# arduinoRGBkaleidoscopeCkt2_v3.net
KiCad netlist of a schematic drawn in EAGLE
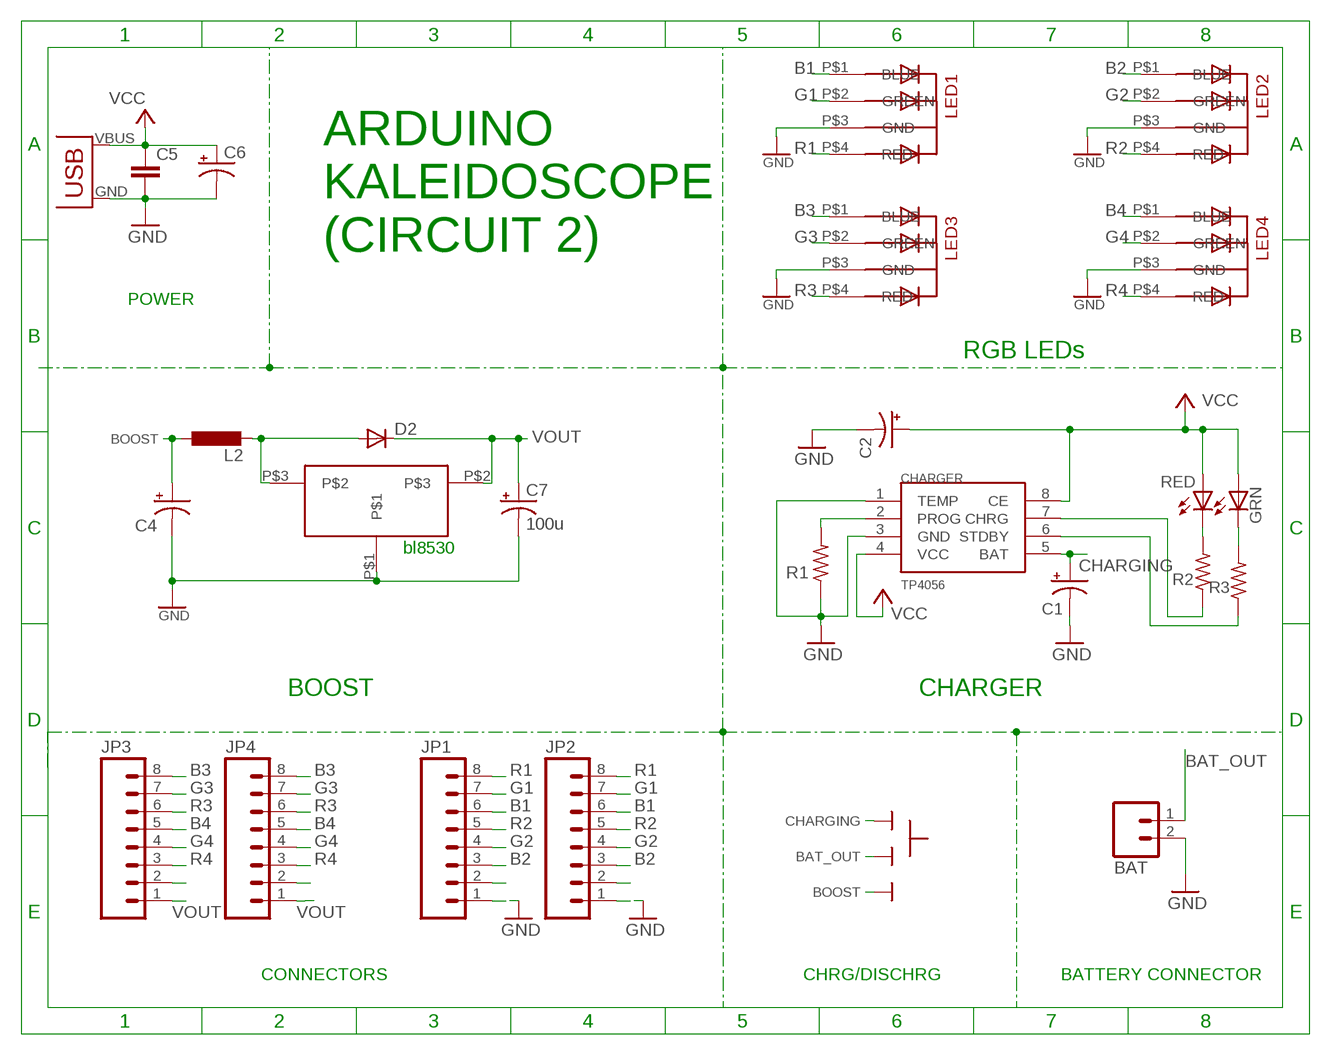
[diagram p0: schematic, sheet 1]

(export (version "E")
  (design (tool "Eeschema 10.0.6"))
  (components
    (comp (ref "BAT")
      (value "M02")
      (footprint "eagle-import:02P")
      (libsource (lib "eagle-import") (part "M02"))
    )
    (comp (ref "BOOST")
      (value "BL8530_5V")
      (footprint "eagle-import:BL8530_5V")
      (libsource (lib "eagle-import") (part "BL8530_5V"))
    )
    (comp (ref "C1")
      (value "10u")
      (footprint "eagle-import:C_6032-28R")
      (libsource (lib "eagle-import") (part "CAP_POL_10V"))
    )
    (comp (ref "C2")
      (value "10u")
      (footprint "eagle-import:C_6032-28R")
      (libsource (lib "eagle-import") (part "CEDT_JANUARY_2015_v7_CAP_POL_10V"))
    )
    (comp (ref "C4")
      (value "10u")
      (footprint "eagle-import:C_6032-28R")
      (libsource (lib "eagle-import") (part "CAP_POL_10V"))
    )
    (comp (ref "C5")
      (value "C-EU025-024X044")
      (footprint "eagle-import:C025-024X044")
      (libsource (lib "eagle-import") (part "C-EU025-024X044"))
    )
    (comp (ref "C6")
      (value "CPOL-USE2,5-6E")
      (footprint "eagle-import:E2,5-6E")
      (libsource (lib "eagle-import") (part "CPOL-USE2,5-6E"))
    )
    (comp (ref "C7")
      (value "100u")
      (footprint "eagle-import:C_6032-28R")
      (libsource (lib "eagle-import") (part "CEDT_JANUARY_2015_v7_CAP_POL_10V"))
    )
    (comp (ref "CHARGER")
      (value "TP4056")
      (footprint "eagle-import:SOP-8")
      (libsource (lib "eagle-import") (part "TP4056"))
    )
    (comp (ref "CHRG/DISCHRG")
      (value "SLIDESWITCH-BIG")
      (footprint "eagle-import:BIGSWITCH")
      (libsource (lib "eagle-import") (part "SLIDESWITCH-BIG"))
    )
    (comp (ref "D2")
      (value "DIODE-DO214AA")
      (footprint "eagle-import:DO214AA")
      (libsource (lib "eagle-import") (part "DIODE-DO214AA"))
    )
    (comp (ref "GRN")
      (value "LED3MM")
      (footprint "eagle-import:CHIPLED_0805")
      (libsource (lib "eagle-import") (part "LEDCHIPLED_0805"))
    )
    (comp (ref "JP1")
      (value "M081X08")
      (footprint "eagle-import:1X08")
      (libsource (lib "eagle-import") (part "M081X08"))
    )
    (comp (ref "JP2")
      (value "M081X08")
      (footprint "eagle-import:1X08")
      (libsource (lib "eagle-import") (part "M081X08"))
    )
    (comp (ref "JP3")
      (value "M081X08")
      (footprint "eagle-import:1X08")
      (libsource (lib "eagle-import") (part "M081X08"))
    )
    (comp (ref "JP4")
      (value "M081X08")
      (footprint "eagle-import:1X08")
      (libsource (lib "eagle-import") (part "M081X08"))
    )
    (comp (ref "L2")
      (value "47uH")
      (footprint "eagle-import:L4532P")
      (libsource (lib "eagle-import") (part "L-EUL4532P"))
    )
    (comp (ref "LED1")
      (value "5MMRGBLED")
      (footprint "eagle-import:LED5MMRGB")
      (libsource (lib "eagle-import") (part "5MMRGBLED"))
    )
    (comp (ref "LED2")
      (value "5MMRGBLED")
      (footprint "eagle-import:LED5MMRGB")
      (libsource (lib "eagle-import") (part "5MMRGBLED"))
    )
    (comp (ref "LED3")
      (value "5MMRGBLED")
      (footprint "eagle-import:LED5MMRGB")
      (libsource (lib "eagle-import") (part "5MMRGBLED"))
    )
    (comp (ref "LED4")
      (value "5MMRGBLED")
      (footprint "eagle-import:LED5MMRGB")
      (libsource (lib "eagle-import") (part "5MMRGBLED"))
    )
    (comp (ref "R1")
      (value "RESISTOR0805")
      (footprint "eagle-import:R0805")
      (libsource (lib "eagle-import") (part "RESISTOR0805"))
    )
    (comp (ref "R2")
      (value "470")
      (footprint "eagle-import:R0805")
      (libsource (lib "eagle-import") (part "RESISTOR0805"))
    )
    (comp (ref "R3")
      (value "470")
      (footprint "eagle-import:R0805")
      (libsource (lib "eagle-import") (part "RESISTOR0805"))
    )
    (comp (ref "RED")
      (value "LED3MM")
      (footprint "eagle-import:CHIPLED_0805")
      (libsource (lib "eagle-import") (part "LEDCHIPLED_0805"))
    )
    (comp (ref "U$1")
      (value "USB(POWER)")
      (footprint "eagle-import:USB(POWER)")
      (libsource (lib "eagle-import") (part "USB(POWER)"))
    )
  )
  (nets
    (net (code "1") (name "/B1") (class "Default")
      (node (ref "JP1") (pin "6") (pinfunction "6_6") (pintype "passive"))
      (node (ref "JP2") (pin "6") (pinfunction "6_6") (pintype "passive"))
      (node (ref "LED1") (pin "P$1") (pinfunction "BLUE_P$1") (pintype "bidirectional"))
    )
    (net (code "2") (name "/B2") (class "Default")
      (node (ref "JP1") (pin "3") (pinfunction "3_3") (pintype "passive"))
      (node (ref "JP2") (pin "3") (pinfunction "3_3") (pintype "passive"))
      (node (ref "LED2") (pin "P$1") (pinfunction "BLUE_P$1") (pintype "bidirectional"))
    )
    (net (code "3") (name "/B3") (class "Default")
      (node (ref "JP3") (pin "8") (pinfunction "8_8") (pintype "passive"))
      (node (ref "JP4") (pin "8") (pinfunction "8_8") (pintype "passive"))
      (node (ref "LED3") (pin "P$1") (pinfunction "BLUE_P$1") (pintype "bidirectional"))
    )
    (net (code "4") (name "/B4") (class "Default")
      (node (ref "JP3") (pin "5") (pinfunction "5_5") (pintype "passive"))
      (node (ref "JP4") (pin "5") (pinfunction "5_5") (pintype "passive"))
      (node (ref "LED4") (pin "P$1") (pinfunction "BLUE_P$1") (pintype "bidirectional"))
    )
    (net (code "5") (name "/BAT_OUT") (class "Default")
      (node (ref "BAT") (pin "1") (pinfunction "1_1") (pintype "passive"))
      (node (ref "CHRG/DISCHRG") (pin "2") (pinfunction "2_2") (pintype "bidirectional"))
    )
    (net (code "6") (name "/BOOST") (class "Default")
      (node (ref "C4") (pin "+") (pinfunction "+_+") (pintype "passive"))
      (node (ref "CHRG/DISCHRG") (pin "3") (pinfunction "3_3") (pintype "bidirectional"))
      (node (ref "L2") (pin "1") (pinfunction "1_1") (pintype "passive"))
    )
    (net (code "7") (name "/CHARGING") (class "Default")
      (node (ref "C1") (pin "+") (pinfunction "+_+") (pintype "passive"))
      (node (ref "CHARGER") (pin "5") (pinfunction "BAT_5") (pintype "bidirectional"))
      (node (ref "CHRG/DISCHRG") (pin "1") (pinfunction "1_1") (pintype "bidirectional"))
    )
    (net (code "8") (name "/G1") (class "Default")
      (node (ref "JP1") (pin "7") (pinfunction "7_7") (pintype "passive"))
      (node (ref "JP2") (pin "7") (pinfunction "7_7") (pintype "passive"))
      (node (ref "LED1") (pin "P$2") (pinfunction "GREEN_P$2") (pintype "bidirectional"))
    )
    (net (code "9") (name "/G2") (class "Default")
      (node (ref "JP1") (pin "4") (pinfunction "4_4") (pintype "passive"))
      (node (ref "JP2") (pin "4") (pinfunction "4_4") (pintype "passive"))
      (node (ref "LED2") (pin "P$2") (pinfunction "GREEN_P$2") (pintype "bidirectional"))
    )
    (net (code "10") (name "/G3") (class "Default")
      (node (ref "JP3") (pin "7") (pinfunction "7_7") (pintype "passive"))
      (node (ref "JP4") (pin "7") (pinfunction "7_7") (pintype "passive"))
      (node (ref "LED3") (pin "P$2") (pinfunction "GREEN_P$2") (pintype "bidirectional"))
    )
    (net (code "11") (name "/G4") (class "Default")
      (node (ref "JP3") (pin "4") (pinfunction "4_4") (pintype "passive"))
      (node (ref "JP4") (pin "4") (pinfunction "4_4") (pintype "passive"))
      (node (ref "LED4") (pin "P$2") (pinfunction "GREEN_P$2") (pintype "bidirectional"))
    )
    (net (code "12") (name "/R1") (class "Default")
      (node (ref "JP1") (pin "8") (pinfunction "8_8") (pintype "passive"))
      (node (ref "JP2") (pin "8") (pinfunction "8_8") (pintype "passive"))
      (node (ref "LED1") (pin "P$4") (pinfunction "RED_P$4") (pintype "bidirectional"))
    )
    (net (code "13") (name "/R2") (class "Default")
      (node (ref "JP1") (pin "5") (pinfunction "5_5") (pintype "passive"))
      (node (ref "JP2") (pin "5") (pinfunction "5_5") (pintype "passive"))
      (node (ref "LED2") (pin "P$4") (pinfunction "RED_P$4") (pintype "bidirectional"))
    )
    (net (code "14") (name "/R3") (class "Default")
      (node (ref "JP3") (pin "6") (pinfunction "6_6") (pintype "passive"))
      (node (ref "JP4") (pin "6") (pinfunction "6_6") (pintype "passive"))
      (node (ref "LED3") (pin "P$4") (pinfunction "RED_P$4") (pintype "bidirectional"))
    )
    (net (code "15") (name "/R4") (class "Default")
      (node (ref "JP3") (pin "3") (pinfunction "3_3") (pintype "passive"))
      (node (ref "JP4") (pin "3") (pinfunction "3_3") (pintype "passive"))
      (node (ref "LED4") (pin "P$4") (pinfunction "RED_P$4") (pintype "bidirectional"))
    )
    (net (code "16") (name "/VOUT") (class "Default")
      (node (ref "BOOST") (pin "P$2") (pinfunction "P$3_P$2") (pintype "bidirectional"))
      (node (ref "C7") (pin "+") (pinfunction "+_+") (pintype "passive"))
      (node (ref "D2") (pin "C") (pinfunction "C_C") (pintype "passive"))
      (node (ref "JP3") (pin "1") (pinfunction "1_1") (pintype "passive"))
      (node (ref "JP4") (pin "1") (pinfunction "1_1") (pintype "passive"))
    )
    (net (code "17") (name "GND") (class "Default")
      (node (ref "BAT") (pin "2") (pinfunction "2_2") (pintype "passive"))
      (node (ref "BOOST") (pin "P$1") (pinfunction "P$1_P$1") (pintype "bidirectional"))
      (node (ref "C1") (pin "-") (pinfunction "-_-") (pintype "passive"))
      (node (ref "C2") (pin "-") (pinfunction "-_-") (pintype "passive"))
      (node (ref "C4") (pin "-") (pinfunction "-_-") (pintype "passive"))
      (node (ref "C5") (pin "2") (pinfunction "2_2") (pintype "passive"))
      (node (ref "C6") (pin "-") (pinfunction "-_-") (pintype "passive"))
      (node (ref "C7") (pin "-") (pinfunction "-_-") (pintype "passive"))
      (node (ref "CHARGER") (pin "1") (pinfunction "TEMP_1") (pintype "bidirectional"))
      (node (ref "CHARGER") (pin "3") (pinfunction "GND_3") (pintype "bidirectional"))
      (node (ref "JP1") (pin "1") (pinfunction "1_1") (pintype "passive"))
      (node (ref "JP2") (pin "1") (pinfunction "1_1") (pintype "passive"))
      (node (ref "LED1") (pin "P$3") (pinfunction "GND_P$3") (pintype "bidirectional"))
      (node (ref "LED2") (pin "P$3") (pinfunction "GND_P$3") (pintype "bidirectional"))
      (node (ref "LED3") (pin "P$3") (pinfunction "GND_P$3") (pintype "bidirectional"))
      (node (ref "LED4") (pin "P$3") (pinfunction "GND_P$3") (pintype "bidirectional"))
      (node (ref "R1") (pin "1") (pinfunction "1_1") (pintype "passive"))
      (node (ref "U$1") (pin "GND") (pinfunction "GND_GND") (pintype "power_in"))
    )
    (net (code "18") (name "Net-(BOOST-P$2)") (class "Default")
      (node (ref "BOOST") (pin "P$3") (pinfunction "P$2_P$3") (pintype "bidirectional"))
      (node (ref "D2") (pin "A") (pinfunction "A_A") (pintype "passive"))
      (node (ref "L2") (pin "2") (pinfunction "2_2") (pintype "passive"))
    )
    (net (code "19") (name "Net-(CHARGER-CHRG)") (class "Default")
      (node (ref "CHARGER") (pin "7") (pinfunction "CHRG_7") (pintype "bidirectional"))
      (node (ref "R2") (pin "1") (pinfunction "1_1") (pintype "passive"))
    )
    (net (code "20") (name "Net-(CHARGER-PROG)") (class "Default")
      (node (ref "CHARGER") (pin "2") (pinfunction "PROG_2") (pintype "bidirectional"))
      (node (ref "R1") (pin "2") (pinfunction "2_2") (pintype "passive"))
    )
    (net (code "21") (name "Net-(CHARGER-STDBY)") (class "Default")
      (node (ref "CHARGER") (pin "6") (pinfunction "STDBY_6") (pintype "bidirectional"))
      (node (ref "R3") (pin "1") (pinfunction "1_1") (pintype "passive"))
    )
    (net (code "22") (name "Net-(GRN-PadC)") (class "Default")
      (node (ref "GRN") (pin "C") (pinfunction "C_C") (pintype "passive"))
      (node (ref "R3") (pin "2") (pinfunction "2_2") (pintype "passive"))
    )
    (net (code "23") (name "Net-(R2-Pad2)") (class "Default")
      (node (ref "R2") (pin "2") (pinfunction "2_2") (pintype "passive"))
      (node (ref "RED") (pin "C") (pinfunction "C_C") (pintype "passive"))
    )
    (net (code "24") (name "VCC") (class "Default")
      (node (ref "C2") (pin "+") (pinfunction "+_+") (pintype "passive"))
      (node (ref "C5") (pin "1") (pinfunction "1_1") (pintype "passive"))
      (node (ref "C6") (pin "+") (pinfunction "+_+") (pintype "passive"))
      (node (ref "CHARGER") (pin "4") (pinfunction "VCC_4") (pintype "bidirectional"))
      (node (ref "CHARGER") (pin "8") (pinfunction "CE_8") (pintype "bidirectional"))
      (node (ref "GRN") (pin "A") (pinfunction "A_A") (pintype "passive"))
      (node (ref "RED") (pin "A") (pinfunction "A_A") (pintype "passive"))
      (node (ref "U$1") (pin "VBUS") (pinfunction "VCC_VBUS") (pintype "power_in"))
    )
    (net (code "25") (name "unconnected-(JP1-Pad2)") (class "Default")
      (node (ref "JP1") (pin "2") (pinfunction "2_2") (pintype "passive"))
    )
    (net (code "26") (name "unconnected-(JP2-Pad2)") (class "Default")
      (node (ref "JP2") (pin "2") (pinfunction "2_2") (pintype "passive"))
    )
    (net (code "27") (name "unconnected-(JP3-Pad2)") (class "Default")
      (node (ref "JP3") (pin "2") (pinfunction "2_2") (pintype "passive"))
    )
    (net (code "28") (name "unconnected-(JP4-Pad2)") (class "Default")
      (node (ref "JP4") (pin "2") (pinfunction "2_2") (pintype "passive"))
    )
  )
)
